# RS-232.net
KiCad netlist of a schematic drawn in Altium Designer
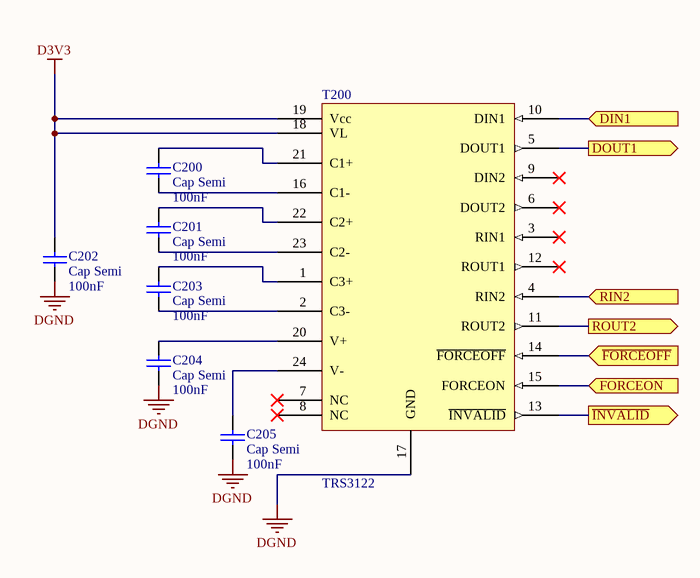
[diagram p0: RS-232.SchDoc]

(export (version "E")
  (design (tool "Eeschema 10.0.6"))
  (components
    (comp (ref "C200")
      (value "Cap Semi")
      (footprint "1608[0603]")
      (description "Capacitor (Semiconductor SIM Model)")
      (fields
        (field (name "ALTIUM_VALUE") "100nF")
        (field (name "PARTNUMBER") "CC0603JRX7R7BB104")
        (field (name "PUBLISHER") "Altium Limited")
      )
      (libsource (lib "Miscellaneous Devices") (part "Cap Semi"))
    )
    (comp (ref "C201")
      (value "Cap Semi")
      (footprint "1608[0603]")
      (description "Capacitor (Semiconductor SIM Model)")
      (fields
        (field (name "ALTIUM_VALUE") "100nF")
        (field (name "PARTNUMBER") "CC0603JRX7R7BB104")
        (field (name "PUBLISHER") "Altium Limited")
      )
      (libsource (lib "Miscellaneous Devices") (part "Cap Semi"))
    )
    (comp (ref "C202")
      (value "Cap Semi")
      (footprint "1608[0603]")
      (description "Capacitor (Semiconductor SIM Model)")
      (fields
        (field (name "ALTIUM_VALUE") "100nF")
        (field (name "PARTNUMBER") "CC0603JRX7R7BB104")
        (field (name "PUBLISHER") "Altium Limited")
      )
      (libsource (lib "Miscellaneous Devices") (part "Cap Semi"))
    )
    (comp (ref "C203")
      (value "Cap Semi")
      (footprint "1608[0603]")
      (description "Capacitor (Semiconductor SIM Model)")
      (fields
        (field (name "ALTIUM_VALUE") "100nF")
        (field (name "PARTNUMBER") "CC0603JRX7R7BB104")
        (field (name "PUBLISHER") "Altium Limited")
      )
      (libsource (lib "Miscellaneous Devices") (part "Cap Semi"))
    )
    (comp (ref "C204")
      (value "Cap Semi")
      (footprint "1608[0603]")
      (description "Capacitor (Semiconductor SIM Model)")
      (fields
        (field (name "ALTIUM_VALUE") "100nF")
        (field (name "PARTNUMBER") "CC0603JRX7R7BB104")
        (field (name "PUBLISHER") "Altium Limited")
      )
      (libsource (lib "Miscellaneous Devices") (part "Cap Semi"))
    )
    (comp (ref "C205")
      (value "Cap Semi")
      (footprint "1608[0603]")
      (description "Capacitor (Semiconductor SIM Model)")
      (fields
        (field (name "ALTIUM_VALUE") "100nF")
        (field (name "PARTNUMBER") "CC0603JRX7R7BB104")
        (field (name "PUBLISHER") "Altium Limited")
      )
      (libsource (lib "Miscellaneous Devices") (part "Cap Semi"))
    )
    (comp (ref "T200")
      (value "TRS3122")
      (footprint "QFN50P485X485X100_HS-25N")
      (fields (field (name "PARTNUMBER") "TRS3122ERGET"))
      (libsource (lib "TRS3122") (part "Component_1"))
    )
  )
  (nets
    (net (code "1") (name "/DIN1") (class "Default")
      (node (ref "T200") (pin "10") (pinfunction "DIN1_10") (pintype "input"))
    )
    (net (code "2") (name "/DOUT1") (class "Default")
      (node (ref "T200") (pin "5") (pinfunction "DOUT1_5") (pintype "output"))
    )
    (net (code "3") (name "/FORCEON") (class "Default")
      (node (ref "T200") (pin "15") (pinfunction "FORCEON_15") (pintype "input"))
    )
    (net (code "4") (name "/RIN2") (class "Default")
      (node (ref "T200") (pin "4") (pinfunction "RIN2_4") (pintype "input"))
    )
    (net (code "5") (name "/ROUT2") (class "Default")
      (node (ref "T200") (pin "11") (pinfunction "ROUT2_11") (pintype "output"))
    )
    (net (code "6") (name "/~{FORCEOFF}") (class "Default")
      (node (ref "T200") (pin "14") (pinfunction "~{FORCEOFF}_14") (pintype "input"))
    )
    (net (code "7") (name "/~{INVALID}") (class "Default")
      (node (ref "T200") (pin "13") (pinfunction "~{INVALID}_13") (pintype "output"))
    )
    (net (code "8") (name "D3V3") (class "Default")
      (node (ref "C202") (pin "1") (pinfunction "1_1") (pintype "passive"))
      (node (ref "T200") (pin "18") (pinfunction "VL_18") (pintype "passive"))
      (node (ref "T200") (pin "19") (pinfunction "Vcc_19") (pintype "passive"))
    )
    (net (code "9") (name "DGND") (class "Default")
      (node (ref "C202") (pin "2") (pinfunction "2_2") (pintype "passive"))
      (node (ref "C204") (pin "2") (pinfunction "2_2") (pintype "passive"))
      (node (ref "C205") (pin "2") (pinfunction "2_2") (pintype "passive"))
      (node (ref "T200") (pin "17") (pinfunction "GND_17") (pintype "passive"))
    )
    (net (code "10") (name "Net-(T200-C1+)") (class "Default")
      (node (ref "C200") (pin "1") (pinfunction "1_1") (pintype "passive"))
      (node (ref "T200") (pin "21") (pinfunction "C1+_21") (pintype "passive"))
    )
    (net (code "11") (name "Net-(T200-C1-)") (class "Default")
      (node (ref "C200") (pin "2") (pinfunction "2_2") (pintype "passive"))
      (node (ref "T200") (pin "16") (pinfunction "C1-_16") (pintype "passive"))
    )
    (net (code "12") (name "Net-(T200-C2+)") (class "Default")
      (node (ref "C201") (pin "1") (pinfunction "1_1") (pintype "passive"))
      (node (ref "T200") (pin "22") (pinfunction "C2+_22") (pintype "passive"))
    )
    (net (code "13") (name "Net-(T200-C2-)") (class "Default")
      (node (ref "C201") (pin "2") (pinfunction "2_2") (pintype "passive"))
      (node (ref "T200") (pin "23") (pinfunction "C2-_23") (pintype "passive"))
    )
    (net (code "14") (name "Net-(T200-C3+)") (class "Default")
      (node (ref "C203") (pin "1") (pinfunction "1_1") (pintype "passive"))
      (node (ref "T200") (pin "1") (pinfunction "C3+_1") (pintype "passive"))
    )
    (net (code "15") (name "Net-(T200-C3-)") (class "Default")
      (node (ref "C203") (pin "2") (pinfunction "2_2") (pintype "passive"))
      (node (ref "T200") (pin "2") (pinfunction "C3-_2") (pintype "passive"))
    )
    (net (code "16") (name "Net-(T200-V+)") (class "Default")
      (node (ref "C204") (pin "1") (pinfunction "1_1") (pintype "passive"))
      (node (ref "T200") (pin "20") (pinfunction "V+_20") (pintype "passive"))
    )
    (net (code "17") (name "Net-(T200-V-)") (class "Default")
      (node (ref "C205") (pin "1") (pinfunction "1_1") (pintype "passive"))
      (node (ref "T200") (pin "24") (pinfunction "V-_24") (pintype "passive"))
    )
    (net (code "18") (name "unconnected-(T200-DIN2-Pad9)") (class "Default")
      (node (ref "T200") (pin "9") (pinfunction "DIN2_9") (pintype "input+no_connect"))
    )
    (net (code "19") (name "unconnected-(T200-DOUT2-Pad6)") (class "Default")
      (node (ref "T200") (pin "6") (pinfunction "DOUT2_6") (pintype "output+no_connect"))
    )
    (net (code "20") (name "unconnected-(T200-NC-Pad7)") (class "Default")
      (node (ref "T200") (pin "7") (pinfunction "NC_7") (pintype "passive+no_connect"))
    )
    (net (code "21") (name "unconnected-(T200-NC-Pad8)") (class "Default")
      (node (ref "T200") (pin "8") (pinfunction "NC_8") (pintype "passive+no_connect"))
    )
    (net (code "22") (name "unconnected-(T200-RIN1-Pad3)") (class "Default")
      (node (ref "T200") (pin "3") (pinfunction "RIN1_3") (pintype "input+no_connect"))
    )
    (net (code "23") (name "unconnected-(T200-ROUT1-Pad12)") (class "Default")
      (node (ref "T200") (pin "12") (pinfunction "ROUT1_12") (pintype "output+no_connect"))
    )
  )
)
